# MCU_Pins.net
KiCad netlist of a schematic drawn in Altium Designer
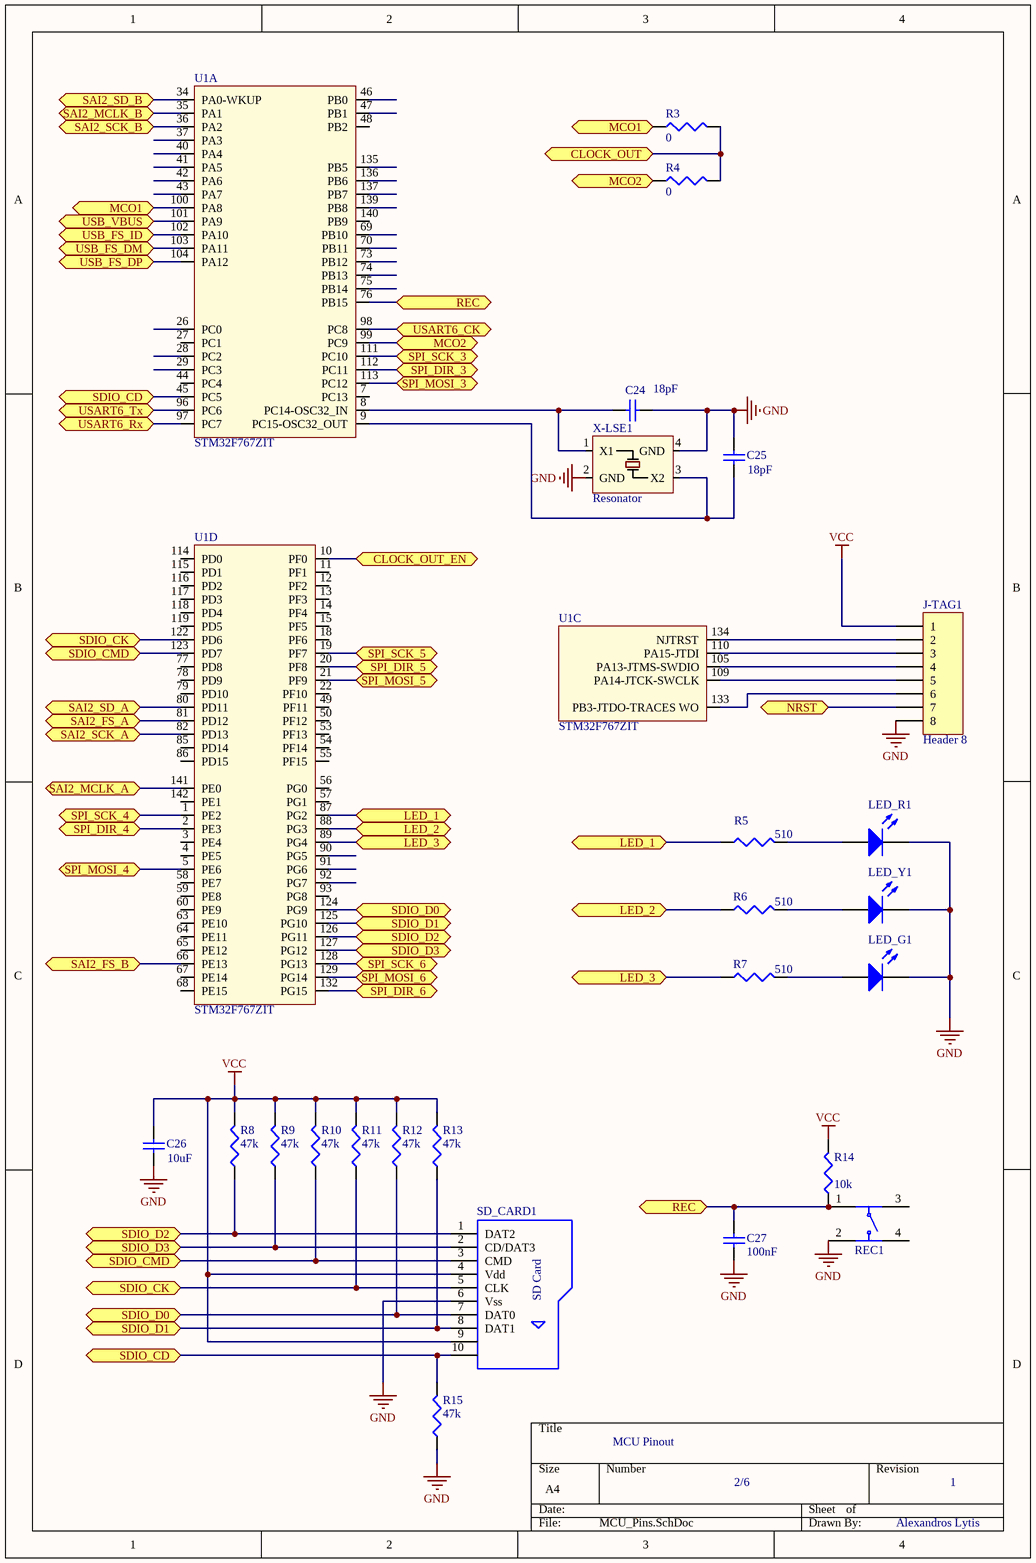
[diagram p0: MCU_Pins.SchDoc]

(export (version "E")
  (design (tool "Eeschema 10.0.6"))
  (components
    (comp (ref "C24")
      (value "18pF")
      (footprint "CAP0603")
      (description "Capacitor (Semiconductor SIM Model)")
      (fields (field (name "Comment") "Cap Semi") (field (name "PUBLISHER") "Altium Limited"))
      (libsource (lib "Miscellaneous Devices") (part "Cap Semi"))
    )
    (comp (ref "C25")
      (value "18pF")
      (footprint "CAP0603")
      (description "Capacitor (Semiconductor SIM Model)")
      (fields (field (name "Comment") "Cap Semi") (field (name "PUBLISHER") "Altium Limited"))
      (libsource (lib "Miscellaneous Devices") (part "Cap Semi"))
    )
    (comp (ref "C26")
      (value "10uF")
      (footprint "CAP0603")
      (description "Capacitor (Semiconductor SIM Model)")
      (fields (field (name "Comment") "Cap Semi") (field (name "PUBLISHER") "Altium Limited"))
      (libsource (lib "Miscellaneous Devices") (part "Cap Semi"))
    )
    (comp (ref "C27")
      (value "100nF")
      (footprint "CAP0603")
      (description "Capacitor (Semiconductor SIM Model)")
      (fields (field (name "Comment") "Cap Semi") (field (name "PUBLISHER") "Altium Limited"))
      (libsource (lib "Miscellaneous Devices") (part "Cap Semi"))
    )
    (comp (ref "J-TAG1")
      (value "Header 8")
      (footprint "HDR1X8")
      (description "Header, 8-Pin")
      (fields (field (name "PUBLISHER") "Altium Limited"))
      (libsource (lib "Miscellaneous Connectors") (part "Header 8"))
    )
    (comp (ref "LED_G1")
      (value "LED2")
      (footprint "1608[0603]")
      (description "Typical RED, GREEN, YELLOW, AMBER GaAs LED")
      (fields (field (name "PUBLISHER") "Altium Limited"))
      (libsource (lib "Miscellaneous Devices") (part "LED2"))
    )
    (comp (ref "LED_R1")
      (value "LED2")
      (footprint "1608[0603]")
      (description "Typical RED, GREEN, YELLOW, AMBER GaAs LED")
      (fields (field (name "PUBLISHER") "Altium Limited"))
      (libsource (lib "Miscellaneous Devices") (part "LED2"))
    )
    (comp (ref "LED_Y1")
      (value "LED2")
      (footprint "1608[0603]")
      (description "Typical RED, GREEN, YELLOW, AMBER GaAs LED")
      (fields (field (name "PUBLISHER") "Altium Limited"))
      (libsource (lib "Miscellaneous Devices") (part "LED2"))
    )
    (comp (ref "R3")
      (value "0")
      (footprint "RES0603")
      (description "Resistor")
      (fields (field (name "Comment") "Res3") (field (name "PUBLISHER") "Altium Limited"))
      (libsource (lib "Miscellaneous Devices") (part "Res3"))
    )
    (comp (ref "R4")
      (value "0")
      (footprint "RES0603")
      (description "Resistor")
      (fields (field (name "Comment") "Res3") (field (name "PUBLISHER") "Altium Limited"))
      (libsource (lib "Miscellaneous Devices") (part "Res3"))
    )
    (comp (ref "R5")
      (value "510")
      (footprint "RES0603")
      (description "Resistor")
      (fields (field (name "Comment") "Res3") (field (name "PUBLISHER") "Altium Limited"))
      (libsource (lib "Miscellaneous Devices") (part "Res3"))
    )
    (comp (ref "R6")
      (value "510")
      (footprint "RES0603")
      (description "Resistor")
      (fields (field (name "Comment") "Res3") (field (name "PUBLISHER") "Altium Limited"))
      (libsource (lib "Miscellaneous Devices") (part "Res3"))
    )
    (comp (ref "R7")
      (value "510")
      (footprint "RES0603")
      (description "Resistor")
      (fields (field (name "Comment") "Res3") (field (name "PUBLISHER") "Altium Limited"))
      (libsource (lib "Miscellaneous Devices") (part "Res3"))
    )
    (comp (ref "R8")
      (value "47k")
      (footprint "RES0603")
      (description "Resistor")
      (fields (field (name "Comment") "Res3") (field (name "PUBLISHER") "Altium Limited"))
      (libsource (lib "Miscellaneous Devices") (part "Res3"))
    )
    (comp (ref "R9")
      (value "47k")
      (footprint "RES0603")
      (description "Resistor")
      (fields (field (name "Comment") "Res3") (field (name "PUBLISHER") "Altium Limited"))
      (libsource (lib "Miscellaneous Devices") (part "Res3"))
    )
    (comp (ref "R10")
      (value "47k")
      (footprint "RES0603")
      (description "Resistor")
      (fields (field (name "Comment") "Res3") (field (name "PUBLISHER") "Altium Limited"))
      (libsource (lib "Miscellaneous Devices") (part "Res3"))
    )
    (comp (ref "R11")
      (value "47k")
      (footprint "RES0603")
      (description "Resistor")
      (fields (field (name "Comment") "Res3") (field (name "PUBLISHER") "Altium Limited"))
      (libsource (lib "Miscellaneous Devices") (part "Res3"))
    )
    (comp (ref "R12")
      (value "47k")
      (footprint "RES0603")
      (description "Resistor")
      (fields (field (name "Comment") "Res3") (field (name "PUBLISHER") "Altium Limited"))
      (libsource (lib "Miscellaneous Devices") (part "Res3"))
    )
    (comp (ref "R13")
      (value "47k")
      (footprint "RES0603")
      (description "Resistor")
      (fields (field (name "Comment") "Res3") (field (name "PUBLISHER") "Altium Limited"))
      (libsource (lib "Miscellaneous Devices") (part "Res3"))
    )
    (comp (ref "R14")
      (value "10k")
      (footprint "RES0603")
      (description "Resistor")
      (fields (field (name "Comment") "Res3") (field (name "PUBLISHER") "Altium Limited"))
      (libsource (lib "Miscellaneous Devices") (part "Res3"))
    )
    (comp (ref "R15")
      (value "47k")
      (footprint "RES0603")
      (description "Resistor")
      (fields (field (name "Comment") "Res3") (field (name "PUBLISHER") "Altium Limited"))
      (libsource (lib "Miscellaneous Devices") (part "Res3"))
    )
    (comp (ref "REC1")
      (value "430152043826")
      (footprint "4301x20438x6")
      (description "WS-TASV 6x6 mm SMD")
      (fields (field (name "MANUFACTURER") "Wurth Elektronik") (field (name "CREATED BY") "Baojun Chen"))
      (libsource (lib "WS-TASV_rev15a") (part "WS-TASV, 430152043826"))
    )
    (comp (ref "SD_CARD1")
      (value "693071010811")
      (footprint "693071010811")
      (description "WR-CRD Micro SD Card Connector Push & Push - 8 pins")
      (fields (field (name "PUBLISHER") "Wurth Elektronik"))
      (libsource (lib "ALTIUM-WR-CRD-rev16c") (part "693071010811"))
    )
    (comp (ref "U1")
      (value "STM32F767ZIT")
      (footprint "TSQFP50P2200X2200X160-144N")
      (libsource (lib "") (part "STM32F767ZIT_1"))
    )
    (comp (ref "X-LSE1")
      (value "Resonator")
      (footprint "SOJ550P380X250-4M")
      (libsource (lib "Custom_Libraries") (part "ABM8G-MHz"))
    )
  )
  (nets
    (net (code "1") (name "/CLOCK_OUT") (class "Default")
      (node (ref "R3") (pin "2") (pinfunction "2_2") (pintype "passive"))
      (node (ref "R4") (pin "2") (pinfunction "2_2") (pintype "passive"))
    )
    (net (code "2") (name "/CLOCK_OUT_EN") (class "Default")
      (node (ref "U1") (pin "10") (pinfunction "PF0_10") (pintype "power_in"))
    )
    (net (code "3") (name "/LED_1") (class "Default")
      (node (ref "R5") (pin "1") (pinfunction "1_1") (pintype "passive"))
      (node (ref "U1") (pin "87") (pinfunction "PG2_87") (pintype "power_in"))
    )
    (net (code "4") (name "/LED_2") (class "Default")
      (node (ref "R6") (pin "1") (pinfunction "1_1") (pintype "passive"))
      (node (ref "U1") (pin "88") (pinfunction "PG3_88") (pintype "power_in"))
    )
    (net (code "5") (name "/LED_3") (class "Default")
      (node (ref "R7") (pin "1") (pinfunction "1_1") (pintype "passive"))
      (node (ref "U1") (pin "89") (pinfunction "PG4_89") (pintype "power_in"))
    )
    (net (code "6") (name "/MCO1") (class "Default")
      (node (ref "R3") (pin "1") (pinfunction "1_1") (pintype "passive"))
      (node (ref "U1") (pin "100") (pinfunction "PA8_100") (pintype "power_in"))
    )
    (net (code "7") (name "/MCO2") (class "Default")
      (node (ref "R4") (pin "1") (pinfunction "1_1") (pintype "passive"))
      (node (ref "U1") (pin "99") (pinfunction "PC9_99") (pintype "power_in"))
    )
    (net (code "8") (name "/NRST") (class "Default")
      (node (ref "J-TAG1") (pin "7") (pinfunction "7_7") (pintype "passive"))
    )
    (net (code "9") (name "/REC") (class "Default")
      (node (ref "C27") (pin "2") (pinfunction "2_2") (pintype "passive"))
      (node (ref "R14") (pin "1") (pinfunction "1_1") (pintype "passive"))
      (node (ref "REC1") (pin "1") (pinfunction "1_1") (pintype "passive"))
      (node (ref "U1") (pin "76") (pinfunction "PB15_76") (pintype "power_in"))
    )
    (net (code "10") (name "/SAI2_FS_A") (class "Default")
      (node (ref "U1") (pin "81") (pinfunction "PD12_81") (pintype "power_in"))
    )
    (net (code "11") (name "/SAI2_FS_B") (class "Default")
      (node (ref "U1") (pin "66") (pinfunction "PE13_66") (pintype "power_in"))
    )
    (net (code "12") (name "/SAI2_MCLK_A") (class "Default")
      (node (ref "U1") (pin "141") (pinfunction "PE0_141") (pintype "power_in"))
    )
    (net (code "13") (name "/SAI2_MCLK_B") (class "Default")
      (node (ref "U1") (pin "35") (pinfunction "PA1_35") (pintype "power_in"))
    )
    (net (code "14") (name "/SAI2_SCK_A") (class "Default")
      (node (ref "U1") (pin "82") (pinfunction "PD13_82") (pintype "power_in"))
    )
    (net (code "15") (name "/SAI2_SCK_B") (class "Default")
      (node (ref "U1") (pin "36") (pinfunction "PA2_36") (pintype "power_in"))
    )
    (net (code "16") (name "/SAI2_SD_A") (class "Default")
      (node (ref "U1") (pin "80") (pinfunction "PD11_80") (pintype "power_in"))
    )
    (net (code "17") (name "/SAI2_SD_B") (class "Default")
      (node (ref "U1") (pin "34") (pinfunction "PA0-WKUP_34") (pintype "power_in"))
    )
    (net (code "18") (name "/SDIO_CD") (class "Default")
      (node (ref "R15") (pin "2") (pinfunction "2_2") (pintype "passive"))
      (node (ref "SD_CARD1") (pin "10") (pinfunction "10_10") (pintype "passive"))
      (node (ref "U1") (pin "45") (pinfunction "PC5_45") (pintype "power_in"))
    )
    (net (code "19") (name "/SDIO_CK") (class "Default")
      (node (ref "R11") (pin "1") (pinfunction "1_1") (pintype "passive"))
      (node (ref "SD_CARD1") (pin "5") (pinfunction "CLK_5") (pintype "passive"))
      (node (ref "U1") (pin "122") (pinfunction "PD6_122") (pintype "power_in"))
    )
    (net (code "20") (name "/SDIO_CMD") (class "Default")
      (node (ref "R10") (pin "1") (pinfunction "1_1") (pintype "passive"))
      (node (ref "SD_CARD1") (pin "3") (pinfunction "CMD_3") (pintype "passive"))
      (node (ref "U1") (pin "123") (pinfunction "PD7_123") (pintype "power_in"))
    )
    (net (code "21") (name "/SDIO_D0") (class "Default")
      (node (ref "R12") (pin "1") (pinfunction "1_1") (pintype "passive"))
      (node (ref "SD_CARD1") (pin "7") (pinfunction "DAT0_7") (pintype "passive"))
      (node (ref "U1") (pin "124") (pinfunction "PG9_124") (pintype "power_in"))
    )
    (net (code "22") (name "/SDIO_D1") (class "Default")
      (node (ref "R13") (pin "1") (pinfunction "1_1") (pintype "passive"))
      (node (ref "SD_CARD1") (pin "8") (pinfunction "DAT1_8") (pintype "passive"))
      (node (ref "U1") (pin "125") (pinfunction "PG10_125") (pintype "power_in"))
    )
    (net (code "23") (name "/SDIO_D2") (class "Default")
      (node (ref "R8") (pin "1") (pinfunction "1_1") (pintype "passive"))
      (node (ref "SD_CARD1") (pin "1") (pinfunction "DAT2_1") (pintype "passive"))
      (node (ref "U1") (pin "126") (pinfunction "PG11_126") (pintype "power_in"))
    )
    (net (code "24") (name "/SDIO_D3") (class "Default")
      (node (ref "R9") (pin "1") (pinfunction "1_1") (pintype "passive"))
      (node (ref "SD_CARD1") (pin "2") (pinfunction "CD/DAT3_2") (pintype "passive"))
      (node (ref "U1") (pin "127") (pinfunction "PG12_127") (pintype "power_in"))
    )
    (net (code "25") (name "/SPI_DIR_3") (class "Default")
      (node (ref "U1") (pin "112") (pinfunction "PC11_112") (pintype "power_in"))
    )
    (net (code "26") (name "/SPI_DIR_4") (class "Default")
      (node (ref "U1") (pin "2") (pinfunction "PE3_2") (pintype "power_in"))
    )
    (net (code "27") (name "/SPI_DIR_5") (class "Default")
      (node (ref "U1") (pin "20") (pinfunction "PF8_20") (pintype "power_in"))
    )
    (net (code "28") (name "/SPI_DIR_6") (class "Default")
      (node (ref "U1") (pin "132") (pinfunction "PG15_132") (pintype "power_in"))
    )
    (net (code "29") (name "/SPI_MOSI_3") (class "Default")
      (node (ref "U1") (pin "113") (pinfunction "PC12_113") (pintype "power_in"))
    )
    (net (code "30") (name "/SPI_MOSI_4") (class "Default")
      (node (ref "U1") (pin "5") (pinfunction "PE6_5") (pintype "power_in"))
    )
    (net (code "31") (name "/SPI_MOSI_5") (class "Default")
      (node (ref "U1") (pin "21") (pinfunction "PF9_21") (pintype "power_in"))
    )
    (net (code "32") (name "/SPI_MOSI_6") (class "Default")
      (node (ref "U1") (pin "129") (pinfunction "PG14_129") (pintype "power_in"))
    )
    (net (code "33") (name "/SPI_SCK_3") (class "Default")
      (node (ref "U1") (pin "111") (pinfunction "PC10_111") (pintype "power_in"))
    )
    (net (code "34") (name "/SPI_SCK_4") (class "Default")
      (node (ref "U1") (pin "1") (pinfunction "PE2_1") (pintype "power_in"))
    )
    (net (code "35") (name "/SPI_SCK_5") (class "Default")
      (node (ref "U1") (pin "19") (pinfunction "PF7_19") (pintype "power_in"))
    )
    (net (code "36") (name "/SPI_SCK_6") (class "Default")
      (node (ref "U1") (pin "128") (pinfunction "PG13_128") (pintype "power_in"))
    )
    (net (code "37") (name "/USART6_CK") (class "Default")
      (node (ref "U1") (pin "98") (pinfunction "PC8_98") (pintype "power_in"))
    )
    (net (code "38") (name "/USART6_Rx") (class "Default")
      (node (ref "U1") (pin "97") (pinfunction "PC7_97") (pintype "power_in"))
    )
    (net (code "39") (name "/USART6_Tx") (class "Default")
      (node (ref "U1") (pin "96") (pinfunction "PC6_96") (pintype "power_in"))
    )
    (net (code "40") (name "/USB_FS_DM") (class "Default")
      (node (ref "U1") (pin "103") (pinfunction "PA11_103") (pintype "power_in"))
    )
    (net (code "41") (name "/USB_FS_DP") (class "Default")
      (node (ref "U1") (pin "104") (pinfunction "PA12_104") (pintype "power_in"))
    )
    (net (code "42") (name "/USB_FS_ID") (class "Default")
      (node (ref "U1") (pin "102") (pinfunction "PA10_102") (pintype "power_in"))
    )
    (net (code "43") (name "/USB_VBUS") (class "Default")
      (node (ref "U1") (pin "101") (pinfunction "PA9_101") (pintype "power_in"))
    )
    (net (code "44") (name "GND") (class "Default")
      (node (ref "C24") (pin "1") (pinfunction "1_1") (pintype "passive"))
      (node (ref "C25") (pin "1") (pinfunction "1_1") (pintype "passive"))
      (node (ref "C26") (pin "1") (pinfunction "1_1") (pintype "passive"))
      (node (ref "C27") (pin "1") (pinfunction "1_1") (pintype "passive"))
      (node (ref "J-TAG1") (pin "8") (pinfunction "8_8") (pintype "passive"))
      (node (ref "LED_G1") (pin "2") (pinfunction "K_2") (pintype "passive"))
      (node (ref "LED_R1") (pin "2") (pinfunction "K_2") (pintype "passive"))
      (node (ref "LED_Y1") (pin "2") (pinfunction "K_2") (pintype "passive"))
      (node (ref "R15") (pin "1") (pinfunction "1_1") (pintype "passive"))
      (node (ref "REC1") (pin "2") (pinfunction "2_2") (pintype "passive"))
      (node (ref "SD_CARD1") (pin "6") (pinfunction "Vss_6") (pintype "passive"))
      (node (ref "X-LSE1") (pin "2") (pinfunction "GND_2") (pintype "passive"))
      (node (ref "X-LSE1") (pin "4") (pinfunction "GND_4") (pintype "passive"))
    )
    (net (code "45") (name "Net-(LED_G1-A)") (class "Default")
      (node (ref "LED_G1") (pin "1") (pinfunction "A_1") (pintype "passive"))
      (node (ref "R7") (pin "2") (pinfunction "2_2") (pintype "passive"))
    )
    (net (code "46") (name "Net-(LED_R1-A)") (class "Default")
      (node (ref "LED_R1") (pin "1") (pinfunction "A_1") (pintype "passive"))
      (node (ref "R5") (pin "2") (pinfunction "2_2") (pintype "passive"))
    )
    (net (code "47") (name "Net-(LED_Y1-A)") (class "Default")
      (node (ref "LED_Y1") (pin "1") (pinfunction "A_1") (pintype "passive"))
      (node (ref "R6") (pin "2") (pinfunction "2_2") (pintype "passive"))
    )
    (net (code "48") (name "Net-(U1A-PC14-OSC32_IN)") (class "Default")
      (node (ref "C24") (pin "2") (pinfunction "2_2") (pintype "passive"))
      (node (ref "U1") (pin "8") (pinfunction "PC14-OSC32_IN_8") (pintype "power_in"))
      (node (ref "X-LSE1") (pin "1") (pinfunction "X1_1") (pintype "passive"))
    )
    (net (code "49") (name "Net-(U1A-PC15-OSC32_OUT)") (class "Default")
      (node (ref "C25") (pin "2") (pinfunction "2_2") (pintype "passive"))
      (node (ref "U1") (pin "9") (pinfunction "PC15-OSC32_OUT_9") (pintype "power_in"))
      (node (ref "X-LSE1") (pin "3") (pinfunction "X2_3") (pintype "passive"))
    )
    (net (code "50") (name "Net-(U1C-NJTRST)") (class "Default")
      (node (ref "J-TAG1") (pin "2") (pinfunction "2_2") (pintype "passive"))
      (node (ref "U1") (pin "134") (pinfunction "NJTRST_134") (pintype "power_in"))
    )
    (net (code "51") (name "Net-(U1C-PA13-JTMS-SWDIO)") (class "Default")
      (node (ref "J-TAG1") (pin "4") (pinfunction "4_4") (pintype "passive"))
      (node (ref "U1") (pin "105") (pinfunction "PA13-JTMS-SWDIO_105") (pintype "power_in"))
    )
    (net (code "52") (name "Net-(U1C-PA14-JTCK-SWCLK)") (class "Default")
      (node (ref "J-TAG1") (pin "5") (pinfunction "5_5") (pintype "passive"))
      (node (ref "U1") (pin "109") (pinfunction "PA14-JTCK-SWCLK_109") (pintype "power_in"))
    )
    (net (code "53") (name "Net-(U1C-PA15-JTDI)") (class "Default")
      (node (ref "J-TAG1") (pin "3") (pinfunction "3_3") (pintype "passive"))
      (node (ref "U1") (pin "110") (pinfunction "PA15-JTDI_110") (pintype "power_in"))
    )
    (net (code "54") (name "Net-(U1C-PB3-JTDO-TRACES_WO)") (class "Default")
      (node (ref "J-TAG1") (pin "6") (pinfunction "6_6") (pintype "passive"))
      (node (ref "U1") (pin "133") (pinfunction "PB3-JTDO-TRACES_WO_133") (pintype "power_in"))
    )
    (net (code "55") (name "VCC") (class "Default")
      (node (ref "C26") (pin "2") (pinfunction "2_2") (pintype "passive"))
      (node (ref "J-TAG1") (pin "1") (pinfunction "1_1") (pintype "passive"))
      (node (ref "R10") (pin "2") (pinfunction "2_2") (pintype "passive"))
      (node (ref "R11") (pin "2") (pinfunction "2_2") (pintype "passive"))
      (node (ref "R12") (pin "2") (pinfunction "2_2") (pintype "passive"))
      (node (ref "R13") (pin "2") (pinfunction "2_2") (pintype "passive"))
      (node (ref "R14") (pin "2") (pinfunction "2_2") (pintype "passive"))
      (node (ref "R8") (pin "2") (pinfunction "2_2") (pintype "passive"))
      (node (ref "R9") (pin "2") (pinfunction "2_2") (pintype "passive"))
      (node (ref "SD_CARD1") (pin "4") (pinfunction "Vdd_4") (pintype "passive"))
      (node (ref "SD_CARD1") (pin "9") (pinfunction "9_9") (pintype "passive"))
    )
    (net (code "56") (name "unconnected-(REC1-Pad3)") (class "Default")
      (node (ref "REC1") (pin "3") (pinfunction "3_3") (pintype "passive"))
    )
    (net (code "57") (name "unconnected-(REC1-Pad4)") (class "Default")
      (node (ref "REC1") (pin "4") (pinfunction "4_4") (pintype "passive"))
    )
    (net (code "58") (name "unconnected-(U1A-PA3-Pad37)") (class "Default")
      (node (ref "U1") (pin "37") (pinfunction "PA3_37") (pintype "power_in"))
    )
    (net (code "59") (name "unconnected-(U1A-PA4-Pad40)") (class "Default")
      (node (ref "U1") (pin "40") (pinfunction "PA4_40") (pintype "power_in"))
    )
    (net (code "60") (name "unconnected-(U1A-PA5-Pad41)") (class "Default")
      (node (ref "U1") (pin "41") (pinfunction "PA5_41") (pintype "power_in"))
    )
    (net (code "61") (name "unconnected-(U1A-PA6-Pad42)") (class "Default")
      (node (ref "U1") (pin "42") (pinfunction "PA6_42") (pintype "power_in"))
    )
    (net (code "62") (name "unconnected-(U1A-PA7-Pad43)") (class "Default")
      (node (ref "U1") (pin "43") (pinfunction "PA7_43") (pintype "power_in"))
    )
    (net (code "63") (name "unconnected-(U1A-PB0-Pad46)") (class "Default")
      (node (ref "U1") (pin "46") (pinfunction "PB0_46") (pintype "power_in"))
    )
    (net (code "64") (name "unconnected-(U1A-PB1-Pad47)") (class "Default")
      (node (ref "U1") (pin "47") (pinfunction "PB1_47") (pintype "power_in"))
    )
    (net (code "65") (name "unconnected-(U1A-PB2-Pad48)") (class "Default")
      (node (ref "U1") (pin "48") (pinfunction "PB2_48") (pintype "power_in"))
    )
    (net (code "66") (name "unconnected-(U1A-PB5-Pad135)") (class "Default")
      (node (ref "U1") (pin "135") (pinfunction "PB5_135") (pintype "power_in"))
    )
    (net (code "67") (name "unconnected-(U1A-PB6-Pad136)") (class "Default")
      (node (ref "U1") (pin "136") (pinfunction "PB6_136") (pintype "power_in"))
    )
    (net (code "68") (name "unconnected-(U1A-PB7-Pad137)") (class "Default")
      (node (ref "U1") (pin "137") (pinfunction "PB7_137") (pintype "power_in"))
    )
    (net (code "69") (name "unconnected-(U1A-PB8-Pad139)") (class "Default")
      (node (ref "U1") (pin "139") (pinfunction "PB8_139") (pintype "power_in"))
    )
    (net (code "70") (name "unconnected-(U1A-PB9-Pad140)") (class "Default")
      (node (ref "U1") (pin "140") (pinfunction "PB9_140") (pintype "power_in"))
    )
    (net (code "71") (name "unconnected-(U1A-PB10-Pad69)") (class "Default")
      (node (ref "U1") (pin "69") (pinfunction "PB10_69") (pintype "power_in"))
    )
    (net (code "72") (name "unconnected-(U1A-PB11-Pad70)") (class "Default")
      (node (ref "U1") (pin "70") (pinfunction "PB11_70") (pintype "power_in"))
    )
    (net (code "73") (name "unconnected-(U1A-PB12-Pad73)") (class "Default")
      (node (ref "U1") (pin "73") (pinfunction "PB12_73") (pintype "power_in"))
    )
    (net (code "74") (name "unconnected-(U1A-PB13-Pad74)") (class "Default")
      (node (ref "U1") (pin "74") (pinfunction "PB13_74") (pintype "power_in"))
    )
    (net (code "75") (name "unconnected-(U1A-PB14-Pad75)") (class "Default")
      (node (ref "U1") (pin "75") (pinfunction "PB14_75") (pintype "power_in"))
    )
    (net (code "76") (name "unconnected-(U1A-PC0-Pad26)") (class "Default")
      (node (ref "U1") (pin "26") (pinfunction "PC0_26") (pintype "power_in"))
    )
    (net (code "77") (name "unconnected-(U1A-PC1-Pad27)") (class "Default")
      (node (ref "U1") (pin "27") (pinfunction "PC1_27") (pintype "power_in"))
    )
    (net (code "78") (name "unconnected-(U1A-PC2-Pad28)") (class "Default")
      (node (ref "U1") (pin "28") (pinfunction "PC2_28") (pintype "power_in"))
    )
    (net (code "79") (name "unconnected-(U1A-PC3-Pad29)") (class "Default")
      (node (ref "U1") (pin "29") (pinfunction "PC3_29") (pintype "power_in"))
    )
    (net (code "80") (name "unconnected-(U1A-PC4-Pad44)") (class "Default")
      (node (ref "U1") (pin "44") (pinfunction "PC4_44") (pintype "power_in"))
    )
    (net (code "81") (name "unconnected-(U1A-PC13-Pad7)") (class "Default")
      (node (ref "U1") (pin "7") (pinfunction "PC13_7") (pintype "power_in"))
    )
    (net (code "82") (name "unconnected-(U1D-PD0-Pad114)") (class "Default")
      (node (ref "U1") (pin "114") (pinfunction "PD0_114") (pintype "power_in"))
    )
    (net (code "83") (name "unconnected-(U1D-PD1-Pad115)") (class "Default")
      (node (ref "U1") (pin "115") (pinfunction "PD1_115") (pintype "power_in"))
    )
    (net (code "84") (name "unconnected-(U1D-PD2-Pad116)") (class "Default")
      (node (ref "U1") (pin "116") (pinfunction "PD2_116") (pintype "power_in"))
    )
    (net (code "85") (name "unconnected-(U1D-PD3-Pad117)") (class "Default")
      (node (ref "U1") (pin "117") (pinfunction "PD3_117") (pintype "power_in"))
    )
    (net (code "86") (name "unconnected-(U1D-PD4-Pad118)") (class "Default")
      (node (ref "U1") (pin "118") (pinfunction "PD4_118") (pintype "power_in"))
    )
    (net (code "87") (name "unconnected-(U1D-PD5-Pad119)") (class "Default")
      (node (ref "U1") (pin "119") (pinfunction "PD5_119") (pintype "power_in"))
    )
    (net (code "88") (name "unconnected-(U1D-PD8-Pad77)") (class "Default")
      (node (ref "U1") (pin "77") (pinfunction "PD8_77") (pintype "power_in"))
    )
    (net (code "89") (name "unconnected-(U1D-PD9-Pad78)") (class "Default")
      (node (ref "U1") (pin "78") (pinfunction "PD9_78") (pintype "power_in"))
    )
    (net (code "90") (name "unconnected-(U1D-PD10-Pad79)") (class "Default")
      (node (ref "U1") (pin "79") (pinfunction "PD10_79") (pintype "power_in"))
    )
    (net (code "91") (name "unconnected-(U1D-PD14-Pad85)") (class "Default")
      (node (ref "U1") (pin "85") (pinfunction "PD14_85") (pintype "power_in"))
    )
    (net (code "92") (name "unconnected-(U1D-PD15-Pad86)") (class "Default")
      (node (ref "U1") (pin "86") (pinfunction "PD15_86") (pintype "power_in"))
    )
    (net (code "93") (name "unconnected-(U1D-PE1-Pad142)") (class "Default")
      (node (ref "U1") (pin "142") (pinfunction "PE1_142") (pintype "power_in"))
    )
    (net (code "94") (name "unconnected-(U1D-PE4-Pad3)") (class "Default")
      (node (ref "U1") (pin "3") (pinfunction "PE4_3") (pintype "power_in"))
    )
    (net (code "95") (name "unconnected-(U1D-PE5-Pad4)") (class "Default")
      (node (ref "U1") (pin "4") (pinfunction "PE5_4") (pintype "power_in"))
    )
    (net (code "96") (name "unconnected-(U1D-PE7-Pad58)") (class "Default")
      (node (ref "U1") (pin "58") (pinfunction "PE7_58") (pintype "power_in"))
    )
    (net (code "97") (name "unconnected-(U1D-PE8-Pad59)") (class "Default")
      (node (ref "U1") (pin "59") (pinfunction "PE8_59") (pintype "power_in"))
    )
    (net (code "98") (name "unconnected-(U1D-PE9-Pad60)") (class "Default")
      (node (ref "U1") (pin "60") (pinfunction "PE9_60") (pintype "power_in"))
    )
    (net (code "99") (name "unconnected-(U1D-PE10-Pad63)") (class "Default")
      (node (ref "U1") (pin "63") (pinfunction "PE10_63") (pintype "power_in"))
    )
    (net (code "100") (name "unconnected-(U1D-PE11-Pad64)") (class "Default")
      (node (ref "U1") (pin "64") (pinfunction "PE11_64") (pintype "power_in"))
    )
    (net (code "101") (name "unconnected-(U1D-PE12-Pad65)") (class "Default")
      (node (ref "U1") (pin "65") (pinfunction "PE12_65") (pintype "power_in"))
    )
    (net (code "102") (name "unconnected-(U1D-PE14-Pad67)") (class "Default")
      (node (ref "U1") (pin "67") (pinfunction "PE14_67") (pintype "power_in"))
    )
    (net (code "103") (name "unconnected-(U1D-PE15-Pad68)") (class "Default")
      (node (ref "U1") (pin "68") (pinfunction "PE15_68") (pintype "power_in"))
    )
    (net (code "104") (name "unconnected-(U1D-PF1-Pad11)") (class "Default")
      (node (ref "U1") (pin "11") (pinfunction "PF1_11") (pintype "power_in"))
    )
    (net (code "105") (name "unconnected-(U1D-PF2-Pad12)") (class "Default")
      (node (ref "U1") (pin "12") (pinfunction "PF2_12") (pintype "power_in"))
    )
    (net (code "106") (name "unconnected-(U1D-PF3-Pad13)") (class "Default")
      (node (ref "U1") (pin "13") (pinfunction "PF3_13") (pintype "power_in"))
    )
    (net (code "107") (name "unconnected-(U1D-PF4-Pad14)") (class "Default")
      (node (ref "U1") (pin "14") (pinfunction "PF4_14") (pintype "power_in"))
    )
    (net (code "108") (name "unconnected-(U1D-PF5-Pad15)") (class "Default")
      (node (ref "U1") (pin "15") (pinfunction "PF5_15") (pintype "power_in"))
    )
    (net (code "109") (name "unconnected-(U1D-PF6-Pad18)") (class "Default")
      (node (ref "U1") (pin "18") (pinfunction "PF6_18") (pintype "power_in"))
    )
    (net (code "110") (name "unconnected-(U1D-PF10-Pad22)") (class "Default")
      (node (ref "U1") (pin "22") (pinfunction "PF10_22") (pintype "power_in"))
    )
    (net (code "111") (name "unconnected-(U1D-PF11-Pad49)") (class "Default")
      (node (ref "U1") (pin "49") (pinfunction "PF11_49") (pintype "power_in"))
    )
    (net (code "112") (name "unconnected-(U1D-PF12-Pad50)") (class "Default")
      (node (ref "U1") (pin "50") (pinfunction "PF12_50") (pintype "power_in"))
    )
    (net (code "113") (name "unconnected-(U1D-PF13-Pad53)") (class "Default")
      (node (ref "U1") (pin "53") (pinfunction "PF13_53") (pintype "power_in"))
    )
    (net (code "114") (name "unconnected-(U1D-PF14-Pad54)") (class "Default")
      (node (ref "U1") (pin "54") (pinfunction "PF14_54") (pintype "power_in"))
    )
    (net (code "115") (name "unconnected-(U1D-PF15-Pad55)") (class "Default")
      (node (ref "U1") (pin "55") (pinfunction "PF15_55") (pintype "power_in"))
    )
    (net (code "116") (name "unconnected-(U1D-PG0-Pad56)") (class "Default")
      (node (ref "U1") (pin "56") (pinfunction "PG0_56") (pintype "power_in"))
    )
    (net (code "117") (name "unconnected-(U1D-PG1-Pad57)") (class "Default")
      (node (ref "U1") (pin "57") (pinfunction "PG1_57") (pintype "power_in"))
    )
    (net (code "118") (name "unconnected-(U1D-PG5-Pad90)") (class "Default")
      (node (ref "U1") (pin "90") (pinfunction "PG5_90") (pintype "power_in"))
    )
    (net (code "119") (name "unconnected-(U1D-PG6-Pad91)") (class "Default")
      (node (ref "U1") (pin "91") (pinfunction "PG6_91") (pintype "power_in"))
    )
    (net (code "120") (name "unconnected-(U1D-PG7-Pad92)") (class "Default")
      (node (ref "U1") (pin "92") (pinfunction "PG7_92") (pintype "power_in"))
    )
    (net (code "121") (name "unconnected-(U1D-PG8-Pad93)") (class "Default")
      (node (ref "U1") (pin "93") (pinfunction "PG8_93") (pintype "power_in"))
    )
  )
)
